# relay.net
KiCad netlist of a schematic drawn in Altium Designer
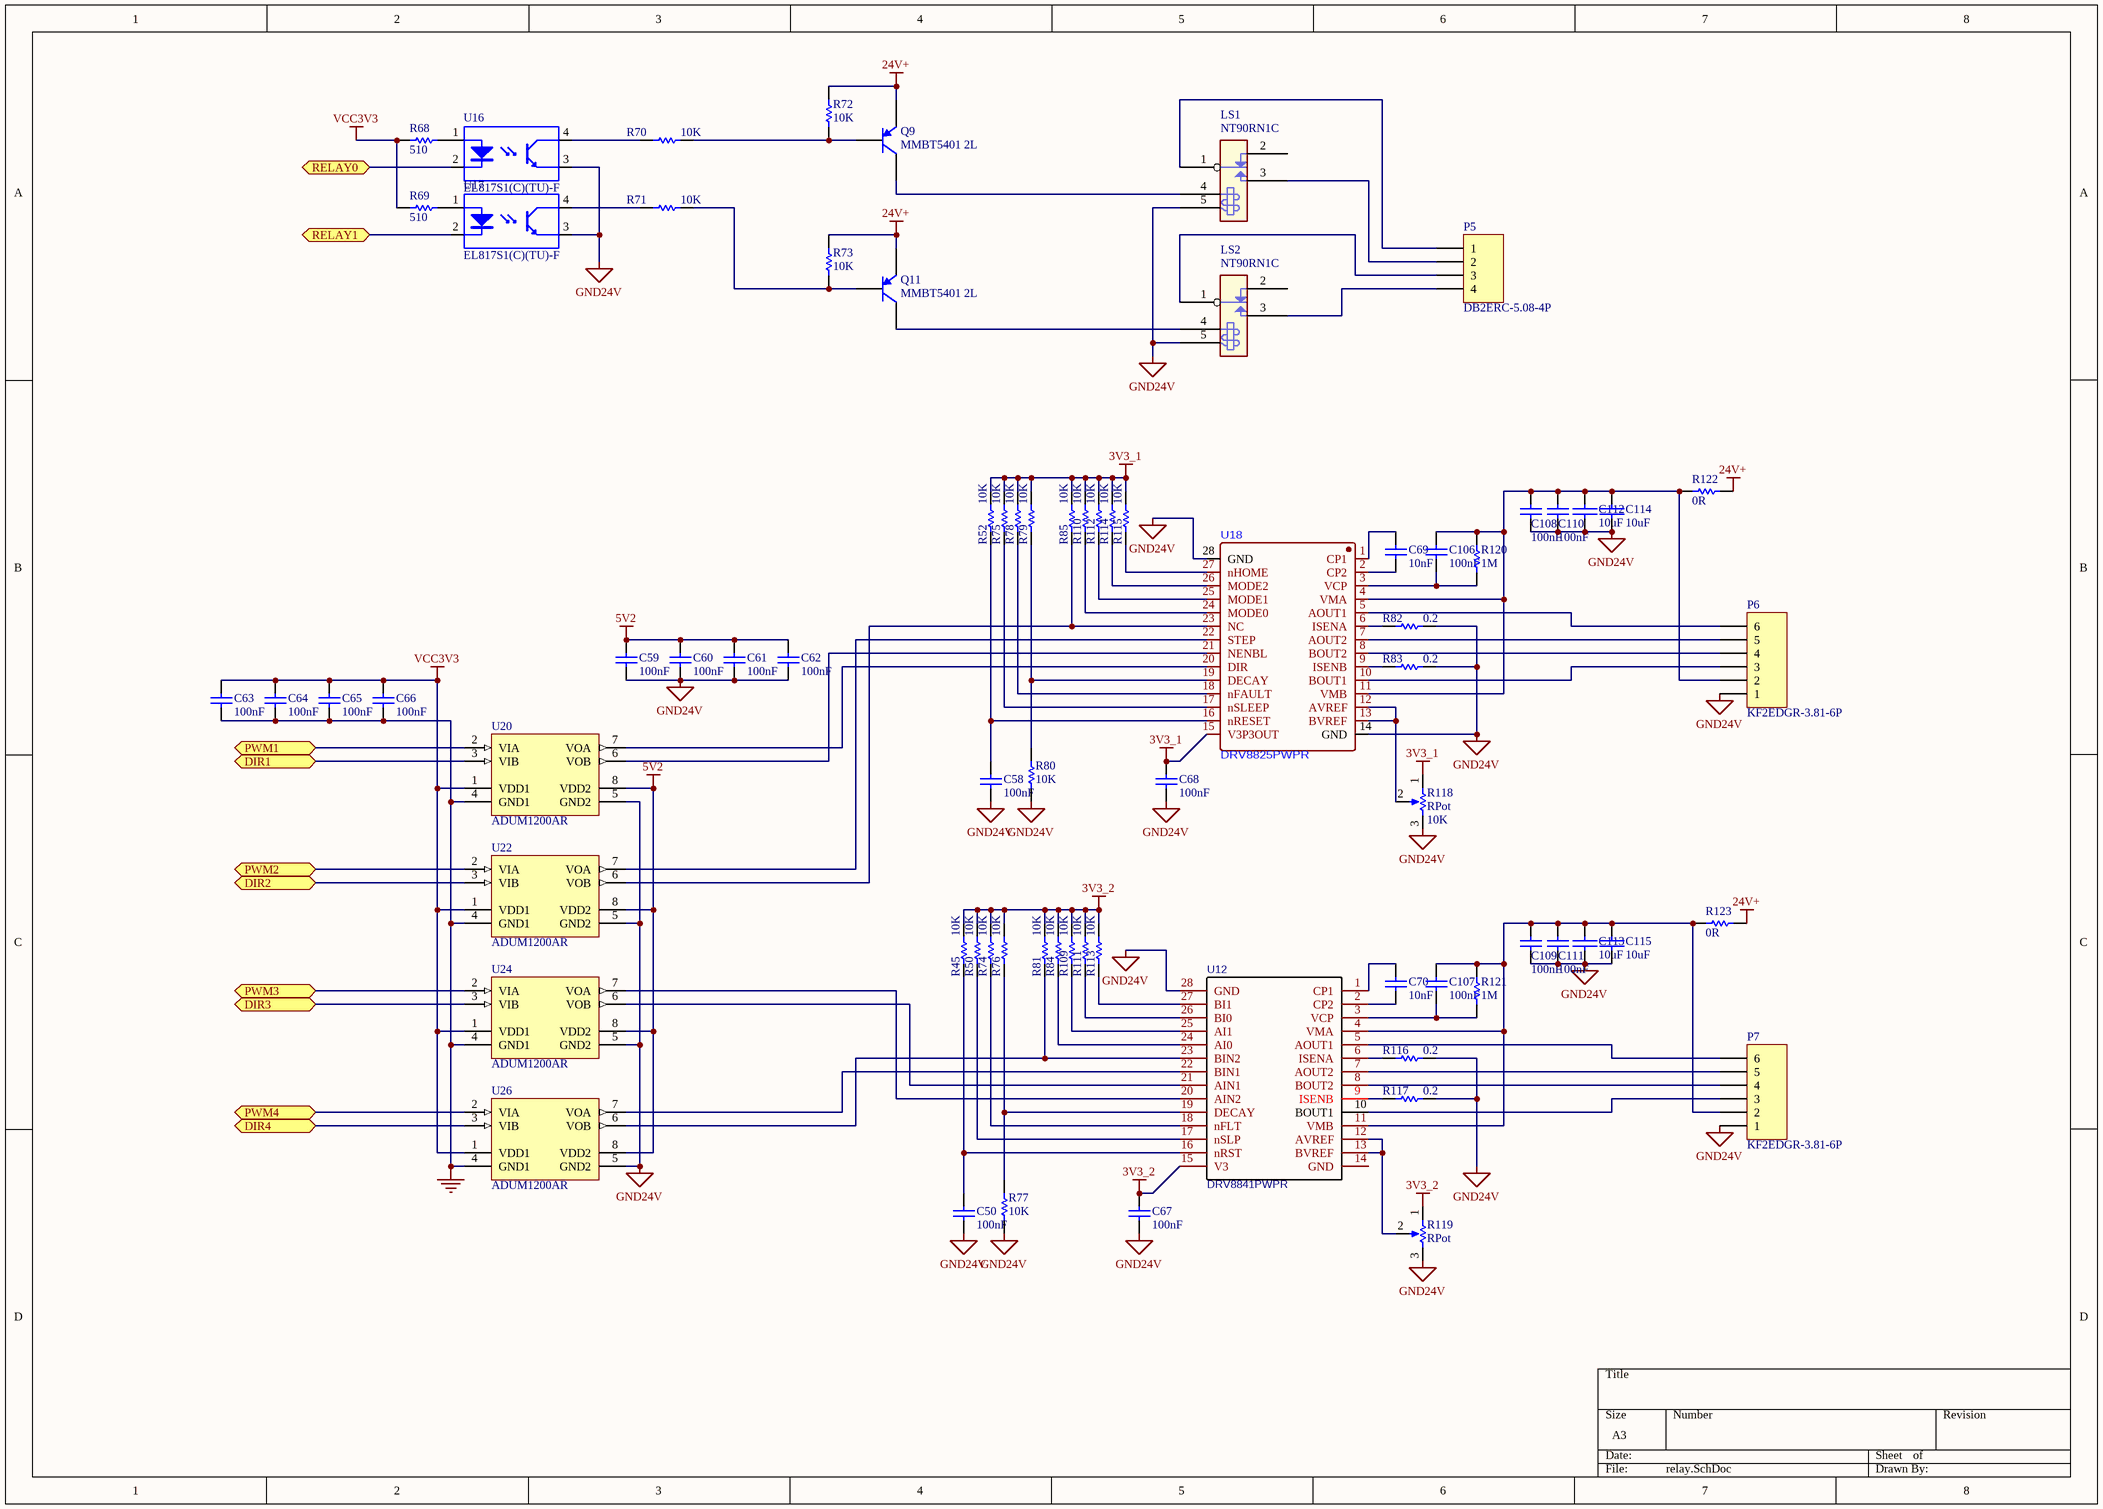
[diagram p0: relay.SchDoc]

(export (version "E")
  (design (tool "Eeschema 10.0.6"))
  (components
    (comp (ref "C50")
      (value "100nF")
      (footprint "0805_C")
      (description "贴片电容")
      (libsource (lib "Miscellaneous Devices LC") (part "0805 100nF(104) 10% 50V"))
    )
    (comp (ref "C58")
      (value "100nF")
      (footprint "0805_C")
      (description "贴片电容")
      (libsource (lib "Miscellaneous Devices LC") (part "0805 100nF(104) 10% 50V"))
    )
    (comp (ref "C59")
      (value "100nF")
      (footprint "0805_C")
      (description "贴片电容")
      (libsource (lib "Miscellaneous Devices LC") (part "0805 100nF(104) 10% 50V"))
    )
    (comp (ref "C60")
      (value "100nF")
      (footprint "0805_C")
      (description "贴片电容")
      (libsource (lib "Miscellaneous Devices LC") (part "0805 100nF(104) 10% 50V"))
    )
    (comp (ref "C61")
      (value "100nF")
      (footprint "0805_C")
      (description "贴片电容")
      (libsource (lib "Miscellaneous Devices LC") (part "0805 100nF(104) 10% 50V"))
    )
    (comp (ref "C62")
      (value "100nF")
      (footprint "0805_C")
      (description "贴片电容")
      (libsource (lib "Miscellaneous Devices LC") (part "0805 100nF(104) 10% 50V"))
    )
    (comp (ref "C63")
      (value "100nF")
      (footprint "0805_C")
      (description "贴片电容")
      (libsource (lib "Miscellaneous Devices LC") (part "0805 100nF(104) 10% 50V"))
    )
    (comp (ref "C64")
      (value "100nF")
      (footprint "0805_C")
      (description "贴片电容")
      (libsource (lib "Miscellaneous Devices LC") (part "0805 100nF(104) 10% 50V"))
    )
    (comp (ref "C65")
      (value "100nF")
      (footprint "0805_C")
      (description "贴片电容")
      (libsource (lib "Miscellaneous Devices LC") (part "0805 100nF(104) 10% 50V"))
    )
    (comp (ref "C66")
      (value "100nF")
      (footprint "0805_C")
      (description "贴片电容")
      (libsource (lib "Miscellaneous Devices LC") (part "0805 100nF(104) 10% 50V"))
    )
    (comp (ref "C67")
      (value "100nF")
      (footprint "0805_C")
      (description "贴片电容")
      (libsource (lib "Miscellaneous Devices LC") (part "0805 100nF(104) 10% 50V"))
    )
    (comp (ref "C68")
      (value "100nF")
      (footprint "0805_C")
      (description "贴片电容")
      (libsource (lib "Miscellaneous Devices LC") (part "0805 100nF(104) 10% 50V"))
    )
    (comp (ref "C69")
      (value "10nF")
      (footprint "0805_C")
      (description "贴片电容")
      (libsource (lib "Miscellaneous Devices LC") (part "0805 100nF(104) 10% 50V"))
    )
    (comp (ref "C70")
      (value "10nF")
      (footprint "0805_C")
      (description "贴片电容")
      (libsource (lib "Miscellaneous Devices LC") (part "0805 100nF(104) 10% 50V"))
    )
    (comp (ref "C106")
      (value "100nF")
      (footprint "0805_C")
      (description "贴片电容")
      (libsource (lib "Miscellaneous Devices LC") (part "0805 100nF(104) 10% 50V"))
    )
    (comp (ref "C107")
      (value "100nF")
      (footprint "0805_C")
      (description "贴片电容")
      (libsource (lib "Miscellaneous Devices LC") (part "0805 100nF(104) 10% 50V"))
    )
    (comp (ref "C108")
      (value "100nF")
      (footprint "0805_C")
      (description "贴片电容")
      (libsource (lib "Miscellaneous Devices LC") (part "0805 100nF(104) 10% 50V"))
    )
    (comp (ref "C109")
      (value "100nF")
      (footprint "0805_C")
      (description "贴片电容")
      (libsource (lib "Miscellaneous Devices LC") (part "0805 100nF(104) 10% 50V"))
    )
    (comp (ref "C110")
      (value "100nF")
      (footprint "0805_C")
      (description "贴片电容")
      (libsource (lib "Miscellaneous Devices LC") (part "0805 100nF(104) 10% 50V"))
    )
    (comp (ref "C111")
      (value "100nF")
      (footprint "0805_C")
      (description "贴片电容")
      (libsource (lib "Miscellaneous Devices LC") (part "0805 100nF(104) 10% 50V"))
    )
    (comp (ref "C112")
      (value "10uF")
      (footprint "0805_C")
      (description "Capacitor")
      (libsource (lib "*") (part "CC"))
    )
    (comp (ref "C113")
      (value "10uF")
      (footprint "0805_C")
      (description "Capacitor")
      (libsource (lib "*") (part "CC"))
    )
    (comp (ref "C114")
      (value "10uF")
      (footprint "0805_C")
      (description "Capacitor")
      (libsource (lib "*") (part "CC"))
    )
    (comp (ref "C115")
      (value "10uF")
      (footprint "0805_C")
      (description "Capacitor")
      (libsource (lib "*") (part "CC"))
    )
    (comp (ref "LS1") (value "NT90RN1C") (libsource (lib "Devices") (part "NT90RN1C")))
    (comp (ref "LS2") (value "NT90RN1C") (libsource (lib "Devices") (part "NT90RN1C")))
    (comp (ref "P5")
      (value "DB2ERC-5.08-4P")
      (footprint "MSTBV 2.5/4-G-5.08")
      (description "Header, 4-Pin, Right Angle")
      (fields (field (name "PUBLISHER") "Altium Limited"))
      (libsource (lib "Miscellaneous Connectors") (part "Header 4H"))
    )
    (comp (ref "P6")
      (value "KF2EDGR-3.81-6P")
      (footprint "MC1.5/6-ST-3.81")
      (description "Header, 6-Pin")
      (fields (field (name "PUBLISHER") "Altium Limited"))
      (libsource (lib "Miscellaneous Connectors") (part "Header 6"))
    )
    (comp (ref "P7")
      (value "KF2EDGR-3.81-6P")
      (footprint "MC1.5/6-ST-3.81")
      (description "Header, 6-Pin")
      (fields (field (name "PUBLISHER") "Altium Limited"))
      (libsource (lib "Miscellaneous Connectors") (part "Header 6"))
    )
    (comp (ref "Q9")
      (value "MMBT5401 2L")
      (footprint "SOT-23(SOT-23-3)")
      (description "三极管")
      (libsource (lib "Miscellaneous Devices LC") (part "SOT-23 MMBT5401 2L"))
    )
    (comp (ref "Q11")
      (value "MMBT5401 2L")
      (footprint "SOT-23(SOT-23-3)")
      (description "三极管")
      (libsource (lib "Miscellaneous Devices LC") (part "SOT-23 MMBT5401 2L"))
    )
    (comp (ref "R45")
      (value "10K")
      (footprint "0805_R")
      (description "Resistor")
      (fields (field (name "PUBLISHER") "Altium Limited"))
      (libsource (lib "Miscellaneous Devices") (part "Res1"))
    )
    (comp (ref "R50")
      (value "10K")
      (footprint "0805_R")
      (description "Resistor")
      (fields (field (name "PUBLISHER") "Altium Limited"))
      (libsource (lib "Miscellaneous Devices") (part "Res1"))
    )
    (comp (ref "R52")
      (value "10K")
      (footprint "0805_R")
      (description "Resistor")
      (fields (field (name "PUBLISHER") "Altium Limited"))
      (libsource (lib "Miscellaneous Devices") (part "Res1"))
    )
    (comp (ref "R68")
      (value "510")
      (footprint "0805_R")
      (description "Resistor")
      (fields (field (name "PUBLISHER") "Altium Limited"))
      (libsource (lib "Miscellaneous Devices") (part "Res1"))
    )
    (comp (ref "R69")
      (value "510")
      (footprint "0805_R")
      (description "Resistor")
      (fields (field (name "PUBLISHER") "Altium Limited"))
      (libsource (lib "Miscellaneous Devices") (part "Res1"))
    )
    (comp (ref "R70")
      (value "10K")
      (footprint "0805_R")
      (description "Resistor")
      (fields (field (name "PUBLISHER") "Altium Limited"))
      (libsource (lib "Miscellaneous Devices") (part "Res1"))
    )
    (comp (ref "R71")
      (value "10K")
      (footprint "0805_R")
      (description "Resistor")
      (fields (field (name "PUBLISHER") "Altium Limited"))
      (libsource (lib "Miscellaneous Devices") (part "Res1"))
    )
    (comp (ref "R72")
      (value "10K")
      (footprint "0805_R")
      (description "Resistor")
      (fields (field (name "PUBLISHER") "Altium Limited"))
      (libsource (lib "Miscellaneous Devices") (part "Res1"))
    )
    (comp (ref "R73")
      (value "10K")
      (footprint "0805_R")
      (description "Resistor")
      (fields (field (name "PUBLISHER") "Altium Limited"))
      (libsource (lib "Miscellaneous Devices") (part "Res1"))
    )
    (comp (ref "R74")
      (value "10K")
      (footprint "0805_R")
      (description "Resistor")
      (fields (field (name "PUBLISHER") "Altium Limited"))
      (libsource (lib "Miscellaneous Devices") (part "Res1"))
    )
    (comp (ref "R75")
      (value "10K")
      (footprint "0805_R")
      (description "Resistor")
      (fields (field (name "PUBLISHER") "Altium Limited"))
      (libsource (lib "Miscellaneous Devices") (part "Res1"))
    )
    (comp (ref "R76")
      (value "10K")
      (footprint "0805_R")
      (description "Resistor")
      (fields (field (name "PUBLISHER") "Altium Limited"))
      (libsource (lib "Miscellaneous Devices") (part "Res1"))
    )
    (comp (ref "R77")
      (value "10K")
      (footprint "0805_R")
      (description "Resistor")
      (fields (field (name "PUBLISHER") "Altium Limited"))
      (libsource (lib "Miscellaneous Devices") (part "Res1"))
    )
    (comp (ref "R78")
      (value "10K")
      (footprint "0805_R")
      (description "Resistor")
      (fields (field (name "PUBLISHER") "Altium Limited"))
      (libsource (lib "Miscellaneous Devices") (part "Res1"))
    )
    (comp (ref "R79")
      (value "10K")
      (footprint "0805_R")
      (description "Resistor")
      (fields (field (name "PUBLISHER") "Altium Limited"))
      (libsource (lib "Miscellaneous Devices") (part "Res1"))
    )
    (comp (ref "R80")
      (value "10K")
      (footprint "0805_R")
      (description "Resistor")
      (fields (field (name "PUBLISHER") "Altium Limited"))
      (libsource (lib "Miscellaneous Devices") (part "Res1"))
    )
    (comp (ref "R81")
      (value "10K")
      (footprint "0805_R")
      (description "Resistor")
      (fields (field (name "PUBLISHER") "Altium Limited"))
      (libsource (lib "Miscellaneous Devices") (part "Res1"))
    )
    (comp (ref "R82")
      (value "0.2")
      (footprint "R1210")
      (description "Resistor")
      (fields (field (name "PUBLISHER") "Altium Limited"))
      (libsource (lib "Miscellaneous Devices") (part "Res1"))
    )
    (comp (ref "R83")
      (value "0.2")
      (footprint "R1210")
      (description "Resistor")
      (fields (field (name "PUBLISHER") "Altium Limited"))
      (libsource (lib "Miscellaneous Devices") (part "Res1"))
    )
    (comp (ref "R84")
      (value "10K")
      (footprint "0805_R")
      (description "Resistor")
      (fields (field (name "PUBLISHER") "Altium Limited"))
      (libsource (lib "Miscellaneous Devices") (part "Res1"))
    )
    (comp (ref "R85")
      (value "10K")
      (footprint "0805_R")
      (description "Resistor")
      (fields (field (name "PUBLISHER") "Altium Limited"))
      (libsource (lib "Miscellaneous Devices") (part "Res1"))
    )
    (comp (ref "R109")
      (value "10K")
      (footprint "0805_R")
      (description "Resistor")
      (fields (field (name "PUBLISHER") "Altium Limited"))
      (libsource (lib "Miscellaneous Devices") (part "Res1"))
    )
    (comp (ref "R110")
      (value "10K")
      (footprint "0805_R")
      (description "Resistor")
      (fields (field (name "PUBLISHER") "Altium Limited"))
      (libsource (lib "Miscellaneous Devices") (part "Res1"))
    )
    (comp (ref "R111")
      (value "10K")
      (footprint "0805_R")
      (description "Resistor")
      (fields (field (name "PUBLISHER") "Altium Limited"))
      (libsource (lib "Miscellaneous Devices") (part "Res1"))
    )
    (comp (ref "R112")
      (value "10K")
      (footprint "0805_R")
      (description "Resistor")
      (fields (field (name "PUBLISHER") "Altium Limited"))
      (libsource (lib "Miscellaneous Devices") (part "Res1"))
    )
    (comp (ref "R113")
      (value "10K")
      (footprint "0805_R")
      (description "Resistor")
      (fields (field (name "PUBLISHER") "Altium Limited"))
      (libsource (lib "Miscellaneous Devices") (part "Res1"))
    )
    (comp (ref "R114")
      (value "10K")
      (footprint "0805_R")
      (description "Resistor")
      (fields (field (name "PUBLISHER") "Altium Limited"))
      (libsource (lib "Miscellaneous Devices") (part "Res1"))
    )
    (comp (ref "R115")
      (value "10K")
      (footprint "0805_R")
      (description "Resistor")
      (fields (field (name "PUBLISHER") "Altium Limited"))
      (libsource (lib "Miscellaneous Devices") (part "Res1"))
    )
    (comp (ref "R116")
      (value "0.2")
      (footprint "R1210")
      (description "Resistor")
      (fields (field (name "PUBLISHER") "Altium Limited"))
      (libsource (lib "Miscellaneous Devices") (part "Res1"))
    )
    (comp (ref "R117")
      (value "0.2")
      (footprint "R1210")
      (description "Resistor")
      (fields (field (name "PUBLISHER") "Altium Limited"))
      (libsource (lib "Miscellaneous Devices") (part "Res1"))
    )
    (comp (ref "R118")
      (value "RPot")
      (footprint "RES-ADJ-TH_3362P")
      (description "Potentiometer")
      (fields (field (name "ALTIUM_VALUE") "10K") (field (name "PUBLISHER") "Altium Limited"))
      (libsource (lib "Miscellaneous Devices") (part "RPot"))
    )
    (comp (ref "R119")
      (value "RPot")
      (footprint "RES-ADJ-TH_3362P")
      (description "Potentiometer")
      (fields (field (name "PUBLISHER") "Altium Limited"))
      (libsource (lib "Miscellaneous Devices") (part "RPot"))
    )
    (comp (ref "R120")
      (value "1M")
      (footprint "0805_R")
      (description "Resistor")
      (fields (field (name "PUBLISHER") "Altium Limited"))
      (libsource (lib "Miscellaneous Devices") (part "Res1"))
    )
    (comp (ref "R121")
      (value "1M")
      (footprint "0805_R")
      (description "Resistor")
      (fields (field (name "PUBLISHER") "Altium Limited"))
      (libsource (lib "Miscellaneous Devices") (part "Res1"))
    )
    (comp (ref "R122")
      (value "0R")
      (footprint "0805_R")
      (description "Resistor")
      (fields (field (name "PUBLISHER") "Altium Limited"))
      (libsource (lib "Miscellaneous Devices") (part "Res1"))
    )
    (comp (ref "R123")
      (value "0R")
      (footprint "0805_R")
      (description "Resistor")
      (fields (field (name "PUBLISHER") "Altium Limited"))
      (libsource (lib "Miscellaneous Devices") (part "Res1"))
    )
    (comp (ref "U12")
      (value "DRV8841PWPR")
      (footprint "HTSSOP-28_L9.8-W4.5-P0.65-LS6.6-BL-EP")
      (fields (field (name "BOM_SUPPLIER PART") "C36542"))
      (libsource (lib "IC") (part "DRV8841PWPR"))
    )
    (comp (ref "U16")
      (value "EL817S1(C)(TU)-F")
      (footprint "LC-SMD-4")
      (libsource (lib "IC") (part "TLP521"))
    )
    (comp (ref "U17")
      (value "EL817S1(C)(TU)-F")
      (footprint "LC-SMD-4")
      (libsource (lib "IC") (part "TLP521"))
    )
    (comp (ref "U18")
      (value "DRV8825PWPR")
      (footprint "HTSSOP_24P_L10.0-W4.4-P0.65-BL-EP")
      (libsource (lib "altium-import") (part "root_0_mirrored_DRV8825PWPR_"))
    )
    (comp (ref "U20")
      (value "ADUM1200AR")
      (footprint "ADI-R-8_N")
      (fields (field (name "MANUFACTURER") "Analog Devices"))
      (libsource (lib "Analog Devices Interface and Isolation Digital Isolators") (part "ADUM1200AR"))
    )
    (comp (ref "U22")
      (value "ADUM1200AR")
      (footprint "ADI-R-8_N")
      (fields (field (name "MANUFACTURER") "Analog Devices"))
      (libsource (lib "Analog Devices Interface and Isolation Digital Isolators") (part "ADUM1200AR"))
    )
    (comp (ref "U24")
      (value "ADUM1200AR")
      (footprint "ADI-R-8_N")
      (fields (field (name "MANUFACTURER") "Analog Devices"))
      (libsource (lib "Analog Devices Interface and Isolation Digital Isolators") (part "ADUM1200AR"))
    )
    (comp (ref "U26")
      (value "ADUM1200AR")
      (footprint "ADI-R-8_N")
      (fields (field (name "MANUFACTURER") "Analog Devices"))
      (libsource (lib "Analog Devices Interface and Isolation Digital Isolators") (part "ADUM1200AR"))
    )
  )
  (nets
    (net (code "1") (name "/DIR1") (class "Default")
      (node (ref "U20") (pin "3") (pinfunction "VIB_3") (pintype "input"))
    )
    (net (code "2") (name "/DIR2") (class "Default")
      (node (ref "U22") (pin "3") (pinfunction "VIB_3") (pintype "input"))
    )
    (net (code "3") (name "/DIR3") (class "Default")
      (node (ref "U24") (pin "3") (pinfunction "VIB_3") (pintype "input"))
    )
    (net (code "4") (name "/DIR4") (class "Default")
      (node (ref "U26") (pin "3") (pinfunction "VIB_3") (pintype "input"))
    )
    (net (code "5") (name "/PWM1") (class "Default")
      (node (ref "U20") (pin "2") (pinfunction "VIA_2") (pintype "input"))
    )
    (net (code "6") (name "/PWM2") (class "Default")
      (node (ref "U22") (pin "2") (pinfunction "VIA_2") (pintype "input"))
    )
    (net (code "7") (name "/PWM3") (class "Default")
      (node (ref "U24") (pin "2") (pinfunction "VIA_2") (pintype "input"))
    )
    (net (code "8") (name "/PWM4") (class "Default")
      (node (ref "U26") (pin "2") (pinfunction "VIA_2") (pintype "input"))
    )
    (net (code "9") (name "/RELAY0") (class "Default")
      (node (ref "U16") (pin "2") (pinfunction "K_2") (pintype "passive"))
    )
    (net (code "10") (name "/RELAY1") (class "Default")
      (node (ref "U17") (pin "2") (pinfunction "K_2") (pintype "passive"))
    )
    (net (code "11") (name "3V3_1") (class "Default")
      (node (ref "C68") (pin "1") (pinfunction "1_1") (pintype "passive"))
      (node (ref "R110") (pin "1") (pinfunction "1_1") (pintype "passive"))
      (node (ref "R112") (pin "1") (pinfunction "1_1") (pintype "passive"))
      (node (ref "R114") (pin "1") (pinfunction "1_1") (pintype "passive"))
      (node (ref "R115") (pin "1") (pinfunction "1_1") (pintype "passive"))
      (node (ref "R118") (pin "1") (pinfunction "TOP_1") (pintype "passive"))
      (node (ref "R52") (pin "1") (pinfunction "1_1") (pintype "passive"))
      (node (ref "R75") (pin "1") (pinfunction "1_1") (pintype "passive"))
      (node (ref "R78") (pin "1") (pinfunction "1_1") (pintype "passive"))
      (node (ref "R79") (pin "1") (pinfunction "1_1") (pintype "passive"))
      (node (ref "R85") (pin "1") (pinfunction "1_1") (pintype "passive"))
      (node (ref "U18") (pin "15") (pinfunction "V3P3OUT_15") (pintype "passive"))
    )
    (net (code "12") (name "3V3_2") (class "Default")
      (node (ref "C67") (pin "1") (pinfunction "1_1") (pintype "passive"))
      (node (ref "R109") (pin "1") (pinfunction "1_1") (pintype "passive"))
      (node (ref "R111") (pin "1") (pinfunction "1_1") (pintype "passive"))
      (node (ref "R113") (pin "1") (pinfunction "1_1") (pintype "passive"))
      (node (ref "R119") (pin "1") (pinfunction "TOP_1") (pintype "passive"))
      (node (ref "R45") (pin "1") (pinfunction "1_1") (pintype "passive"))
      (node (ref "R50") (pin "1") (pinfunction "1_1") (pintype "passive"))
      (node (ref "R74") (pin "1") (pinfunction "1_1") (pintype "passive"))
      (node (ref "R76") (pin "1") (pinfunction "1_1") (pintype "passive"))
      (node (ref "R81") (pin "1") (pinfunction "1_1") (pintype "passive"))
      (node (ref "R84") (pin "1") (pinfunction "1_1") (pintype "passive"))
      (node (ref "U12") (pin "15") (pinfunction "V3_15") (pintype "passive"))
    )
    (net (code "13") (name "5V2") (class "Default")
      (node (ref "C59") (pin "2") (pinfunction "2_2") (pintype "passive"))
      (node (ref "C60") (pin "2") (pinfunction "2_2") (pintype "passive"))
      (node (ref "C61") (pin "2") (pinfunction "2_2") (pintype "passive"))
      (node (ref "C62") (pin "2") (pinfunction "2_2") (pintype "passive"))
      (node (ref "U20") (pin "8") (pinfunction "VDD2_8") (pintype "power_in"))
      (node (ref "U22") (pin "8") (pinfunction "VDD2_8") (pintype "power_in"))
      (node (ref "U24") (pin "8") (pinfunction "VDD2_8") (pintype "power_in"))
      (node (ref "U26") (pin "8") (pinfunction "VDD2_8") (pintype "power_in"))
    )
    (net (code "14") (name "24V+") (class "Default")
      (node (ref "Q11") (pin "2") (pinfunction "E_2") (pintype "passive"))
      (node (ref "Q9") (pin "2") (pinfunction "E_2") (pintype "passive"))
      (node (ref "R122") (pin "2") (pinfunction "2_2") (pintype "passive"))
      (node (ref "R123") (pin "2") (pinfunction "2_2") (pintype "passive"))
      (node (ref "R72") (pin "2") (pinfunction "2_2") (pintype "passive"))
      (node (ref "R73") (pin "2") (pinfunction "2_2") (pintype "passive"))
    )
    (net (code "15") (name "GND") (class "Default")
      (node (ref "C63") (pin "1") (pinfunction "1_1") (pintype "passive"))
      (node (ref "C64") (pin "1") (pinfunction "1_1") (pintype "passive"))
      (node (ref "C65") (pin "1") (pinfunction "1_1") (pintype "passive"))
      (node (ref "C66") (pin "1") (pinfunction "1_1") (pintype "passive"))
      (node (ref "U20") (pin "4") (pinfunction "GND1_4") (pintype "power_in"))
      (node (ref "U22") (pin "4") (pinfunction "GND1_4") (pintype "power_in"))
      (node (ref "U24") (pin "4") (pinfunction "GND1_4") (pintype "power_in"))
      (node (ref "U26") (pin "4") (pinfunction "GND1_4") (pintype "power_in"))
    )
    (net (code "16") (name "GND24V") (class "Default")
      (node (ref "C108") (pin "1") (pinfunction "1_1") (pintype "passive"))
      (node (ref "C109") (pin "1") (pinfunction "1_1") (pintype "passive"))
      (node (ref "C110") (pin "1") (pinfunction "1_1") (pintype "passive"))
      (node (ref "C111") (pin "1") (pinfunction "1_1") (pintype "passive"))
      (node (ref "C112") (pin "1") (pinfunction "1_1") (pintype "passive"))
      (node (ref "C113") (pin "1") (pinfunction "1_1") (pintype "passive"))
      (node (ref "C114") (pin "1") (pinfunction "1_1") (pintype "passive"))
      (node (ref "C115") (pin "1") (pinfunction "1_1") (pintype "passive"))
      (node (ref "C50") (pin "2") (pinfunction "2_2") (pintype "passive"))
      (node (ref "C58") (pin "2") (pinfunction "2_2") (pintype "passive"))
      (node (ref "C59") (pin "1") (pinfunction "1_1") (pintype "passive"))
      (node (ref "C60") (pin "1") (pinfunction "1_1") (pintype "passive"))
      (node (ref "C61") (pin "1") (pinfunction "1_1") (pintype "passive"))
      (node (ref "C62") (pin "1") (pinfunction "1_1") (pintype "passive"))
      (node (ref "C67") (pin "2") (pinfunction "2_2") (pintype "passive"))
      (node (ref "C68") (pin "2") (pinfunction "2_2") (pintype "passive"))
      (node (ref "LS1") (pin "5") (pinfunction "COIL2_5") (pintype "passive"))
      (node (ref "LS2") (pin "5") (pinfunction "COIL2_5") (pintype "passive"))
      (node (ref "P6") (pin "1") (pinfunction "1_1") (pintype "passive"))
      (node (ref "P7") (pin "1") (pinfunction "1_1") (pintype "passive"))
      (node (ref "R116") (pin "1") (pinfunction "1_1") (pintype "passive"))
      (node (ref "R117") (pin "1") (pinfunction "1_1") (pintype "passive"))
      (node (ref "R118") (pin "3") (pinfunction "BOT_3") (pintype "passive"))
      (node (ref "R119") (pin "3") (pinfunction "BOT_3") (pintype "passive"))
      (node (ref "R77") (pin "2") (pinfunction "2_2") (pintype "passive"))
      (node (ref "R80") (pin "2") (pinfunction "2_2") (pintype "passive"))
      (node (ref "R82") (pin "1") (pinfunction "1_1") (pintype "passive"))
      (node (ref "R83") (pin "1") (pinfunction "1_1") (pintype "passive"))
      (node (ref "U12") (pin "28") (pinfunction "GND_28") (pintype "passive"))
      (node (ref "U16") (pin "3") (pinfunction "E_3") (pintype "passive"))
      (node (ref "U17") (pin "3") (pinfunction "E_3") (pintype "passive"))
      (node (ref "U18") (pin "14") (pinfunction "GND_14") (pintype "passive"))
      (node (ref "U18") (pin "28") (pinfunction "GND_28") (pintype "passive"))
      (node (ref "U20") (pin "5") (pinfunction "GND2_5") (pintype "power_in"))
      (node (ref "U22") (pin "5") (pinfunction "GND2_5") (pintype "power_in"))
      (node (ref "U24") (pin "5") (pinfunction "GND2_5") (pintype "power_in"))
      (node (ref "U26") (pin "5") (pinfunction "GND2_5") (pintype "power_in"))
    )
    (net (code "17") (name "Net-(LS1-COIL1)") (class "Default")
      (node (ref "LS1") (pin "4") (pinfunction "COIL1_4") (pintype "passive"))
      (node (ref "Q9") (pin "3") (pinfunction "C_3") (pintype "passive"))
    )
    (net (code "18") (name "Net-(LS1-COMMON)") (class "Default")
      (node (ref "LS1") (pin "1") (pinfunction "COMMON_1") (pintype "passive"))
      (node (ref "P5") (pin "1") (pinfunction "1_1") (pintype "passive"))
    )
    (net (code "19") (name "Net-(LS1-NO)") (class "Default")
      (node (ref "LS1") (pin "3") (pinfunction "NO_3") (pintype "passive"))
      (node (ref "P5") (pin "2") (pinfunction "2_2") (pintype "passive"))
    )
    (net (code "20") (name "Net-(LS2-COIL1)") (class "Default")
      (node (ref "LS2") (pin "4") (pinfunction "COIL1_4") (pintype "passive"))
      (node (ref "Q11") (pin "3") (pinfunction "C_3") (pintype "passive"))
    )
    (net (code "21") (name "Net-(LS2-COMMON)") (class "Default")
      (node (ref "LS2") (pin "1") (pinfunction "COMMON_1") (pintype "passive"))
      (node (ref "P5") (pin "3") (pinfunction "3_3") (pintype "passive"))
    )
    (net (code "22") (name "Net-(LS2-NO)") (class "Default")
      (node (ref "LS2") (pin "3") (pinfunction "NO_3") (pintype "passive"))
      (node (ref "P5") (pin "4") (pinfunction "4_4") (pintype "passive"))
    )
    (net (code "23") (name "Net-(Q9-B)") (class "Default")
      (node (ref "Q9") (pin "1") (pinfunction "B_1") (pintype "passive"))
      (node (ref "R70") (pin "2") (pinfunction "2_2") (pintype "passive"))
      (node (ref "R72") (pin "1") (pinfunction "1_1") (pintype "passive"))
    )
    (net (code "24") (name "Net-(Q11-B)") (class "Default")
      (node (ref "Q11") (pin "1") (pinfunction "B_1") (pintype "passive"))
      (node (ref "R71") (pin "2") (pinfunction "2_2") (pintype "passive"))
      (node (ref "R73") (pin "1") (pinfunction "1_1") (pintype "passive"))
    )
    (net (code "25") (name "Net-(R118-TAP)") (class "Default")
      (node (ref "R118") (pin "2") (pinfunction "TAP_2") (pintype "passive"))
      (node (ref "U18") (pin "12") (pinfunction "AVREF_12") (pintype "passive"))
      (node (ref "U18") (pin "13") (pinfunction "BVREF_13") (pintype "passive"))
    )
    (net (code "26") (name "Net-(R119-TAP)") (class "Default")
      (node (ref "R119") (pin "2") (pinfunction "TAP_2") (pintype "passive"))
      (node (ref "U12") (pin "12") (pinfunction "AVREF_12") (pintype "passive"))
      (node (ref "U12") (pin "13") (pinfunction "BVREF_13") (pintype "passive"))
    )
    (net (code "27") (name "Net-(U12-AI0)") (class "Default")
      (node (ref "R84") (pin "2") (pinfunction "2_2") (pintype "passive"))
      (node (ref "U12") (pin "24") (pinfunction "AI0_24") (pintype "passive"))
    )
    (net (code "28") (name "Net-(U12-AI1)") (class "Default")
      (node (ref "R109") (pin "2") (pinfunction "2_2") (pintype "passive"))
      (node (ref "U12") (pin "25") (pinfunction "AI1_25") (pintype "passive"))
    )
    (net (code "29") (name "Net-(U12-AIN1)") (class "Default")
      (node (ref "U12") (pin "21") (pinfunction "AIN1_21") (pintype "passive"))
      (node (ref "U24") (pin "6") (pinfunction "VOB_6") (pintype "output"))
    )
    (net (code "30") (name "Net-(U12-AIN2)") (class "Default")
      (node (ref "U12") (pin "20") (pinfunction "AIN2_20") (pintype "passive"))
      (node (ref "U24") (pin "7") (pinfunction "VOA_7") (pintype "output"))
    )
    (net (code "31") (name "Net-(U12-AOUT1)") (class "Default")
      (node (ref "P7") (pin "6") (pinfunction "6_6") (pintype "passive"))
      (node (ref "U12") (pin "5") (pinfunction "AOUT1_5") (pintype "passive"))
    )
    (net (code "32") (name "Net-(U12-AOUT2)") (class "Default")
      (node (ref "P7") (pin "5") (pinfunction "5_5") (pintype "passive"))
      (node (ref "U12") (pin "7") (pinfunction "AOUT2_7") (pintype "passive"))
    )
    (net (code "33") (name "Net-(U12-BI0)") (class "Default")
      (node (ref "R111") (pin "2") (pinfunction "2_2") (pintype "passive"))
      (node (ref "U12") (pin "26") (pinfunction "BI0_26") (pintype "passive"))
    )
    (net (code "34") (name "Net-(U12-BI1)") (class "Default")
      (node (ref "R113") (pin "2") (pinfunction "2_2") (pintype "passive"))
      (node (ref "U12") (pin "27") (pinfunction "BI1_27") (pintype "passive"))
    )
    (net (code "35") (name "Net-(U12-BIN1)") (class "Default")
      (node (ref "U12") (pin "22") (pinfunction "BIN1_22") (pintype "passive"))
      (node (ref "U26") (pin "7") (pinfunction "VOA_7") (pintype "output"))
    )
    (net (code "36") (name "Net-(U12-BIN2)") (class "Default")
      (node (ref "R81") (pin "2") (pinfunction "2_2") (pintype "passive"))
      (node (ref "U12") (pin "23") (pinfunction "BIN2_23") (pintype "passive"))
      (node (ref "U26") (pin "6") (pinfunction "VOB_6") (pintype "output"))
    )
    (net (code "37") (name "Net-(U12-BOUT1)") (class "Default")
      (node (ref "P7") (pin "3") (pinfunction "3_3") (pintype "passive"))
      (node (ref "U12") (pin "10") (pinfunction "BOUT1_10") (pintype "passive"))
    )
    (net (code "38") (name "Net-(U12-BOUT2)") (class "Default")
      (node (ref "P7") (pin "4") (pinfunction "4_4") (pintype "passive"))
      (node (ref "U12") (pin "8") (pinfunction "BOUT2_8") (pintype "passive"))
    )
    (net (code "39") (name "Net-(U12-CP1)") (class "Default")
      (node (ref "C70") (pin "1") (pinfunction "1_1") (pintype "passive"))
      (node (ref "U12") (pin "1") (pinfunction "CP1_1") (pintype "passive"))
    )
    (net (code "40") (name "Net-(U12-CP2)") (class "Default")
      (node (ref "C70") (pin "2") (pinfunction "2_2") (pintype "passive"))
      (node (ref "U12") (pin "2") (pinfunction "CP2_2") (pintype "passive"))
    )
    (net (code "41") (name "Net-(U12-DECAY)") (class "Default")
      (node (ref "R76") (pin "2") (pinfunction "2_2") (pintype "passive"))
      (node (ref "R77") (pin "1") (pinfunction "1_1") (pintype "passive"))
      (node (ref "U12") (pin "19") (pinfunction "DECAY_19") (pintype "passive"))
    )
    (net (code "42") (name "Net-(U12-ISENA)") (class "Default")
      (node (ref "R116") (pin "2") (pinfunction "2_2") (pintype "passive"))
      (node (ref "U12") (pin "6") (pinfunction "ISENA_6") (pintype "passive"))
    )
    (net (code "43") (name "Net-(U12-ISENB)") (class "Default")
      (node (ref "R117") (pin "2") (pinfunction "2_2") (pintype "passive"))
      (node (ref "U12") (pin "9") (pinfunction "ISENB_9") (pintype "passive"))
    )
    (net (code "44") (name "Net-(U12-VCP)") (class "Default")
      (node (ref "C107") (pin "1") (pinfunction "1_1") (pintype "passive"))
      (node (ref "R121") (pin "2") (pinfunction "2_2") (pintype "passive"))
      (node (ref "U12") (pin "3") (pinfunction "VCP_3") (pintype "passive"))
    )
    (net (code "45") (name "Net-(U12-VMA)") (class "Default")
      (node (ref "C107") (pin "2") (pinfunction "2_2") (pintype "passive"))
      (node (ref "C109") (pin "2") (pinfunction "2_2") (pintype "passive"))
      (node (ref "C111") (pin "2") (pinfunction "2_2") (pintype "passive"))
      (node (ref "C113") (pin "2") (pinfunction "2_2") (pintype "passive"))
      (node (ref "C115") (pin "2") (pinfunction "2_2") (pintype "passive"))
      (node (ref "P7") (pin "2") (pinfunction "2_2") (pintype "passive"))
      (node (ref "R121") (pin "1") (pinfunction "1_1") (pintype "passive"))
      (node (ref "R123") (pin "1") (pinfunction "1_1") (pintype "passive"))
      (node (ref "U12") (pin "11") (pinfunction "VMB_11") (pintype "passive"))
      (node (ref "U12") (pin "4") (pinfunction "VMA_4") (pintype "passive"))
    )
    (net (code "46") (name "Net-(U12-nFLT)") (class "Default")
      (node (ref "R74") (pin "2") (pinfunction "2_2") (pintype "passive"))
      (node (ref "U12") (pin "18") (pinfunction "nFLT_18") (pintype "passive"))
    )
    (net (code "47") (name "Net-(U12-nRST)") (class "Default")
      (node (ref "C50") (pin "1") (pinfunction "1_1") (pintype "passive"))
      (node (ref "R45") (pin "2") (pinfunction "2_2") (pintype "passive"))
      (node (ref "U12") (pin "16") (pinfunction "nRST_16") (pintype "passive"))
    )
    (net (code "48") (name "Net-(U12-nSLP)") (class "Default")
      (node (ref "R50") (pin "2") (pinfunction "2_2") (pintype "passive"))
      (node (ref "U12") (pin "17") (pinfunction "nSLP_17") (pintype "passive"))
    )
    (net (code "49") (name "Net-(U16-A)") (class "Default")
      (node (ref "R68") (pin "1") (pinfunction "1_1") (pintype "passive"))
      (node (ref "U16") (pin "1") (pinfunction "A_1") (pintype "passive"))
    )
    (net (code "50") (name "Net-(U16-C)") (class "Default")
      (node (ref "R70") (pin "1") (pinfunction "1_1") (pintype "passive"))
      (node (ref "U16") (pin "4") (pinfunction "C_4") (pintype "passive"))
    )
    (net (code "51") (name "Net-(U17-A)") (class "Default")
      (node (ref "R69") (pin "1") (pinfunction "1_1") (pintype "passive"))
      (node (ref "U17") (pin "1") (pinfunction "A_1") (pintype "passive"))
    )
    (net (code "52") (name "Net-(U17-C)") (class "Default")
      (node (ref "R71") (pin "1") (pinfunction "1_1") (pintype "passive"))
      (node (ref "U17") (pin "4") (pinfunction "C_4") (pintype "passive"))
    )
    (net (code "53") (name "Net-(U18-AOUT1)") (class "Default")
      (node (ref "P6") (pin "6") (pinfunction "6_6") (pintype "passive"))
      (node (ref "U18") (pin "5") (pinfunction "AOUT1_5") (pintype "passive"))
    )
    (net (code "54") (name "Net-(U18-AOUT2)") (class "Default")
      (node (ref "P6") (pin "5") (pinfunction "5_5") (pintype "passive"))
      (node (ref "U18") (pin "7") (pinfunction "AOUT2_7") (pintype "passive"))
    )
    (net (code "55") (name "Net-(U18-BOUT1)") (class "Default")
      (node (ref "P6") (pin "3") (pinfunction "3_3") (pintype "passive"))
      (node (ref "U18") (pin "10") (pinfunction "BOUT1_10") (pintype "passive"))
    )
    (net (code "56") (name "Net-(U18-BOUT2)") (class "Default")
      (node (ref "P6") (pin "4") (pinfunction "4_4") (pintype "passive"))
      (node (ref "U18") (pin "8") (pinfunction "BOUT2_8") (pintype "passive"))
    )
    (net (code "57") (name "Net-(U18-CP1)") (class "Default")
      (node (ref "C69") (pin "1") (pinfunction "1_1") (pintype "passive"))
      (node (ref "U18") (pin "1") (pinfunction "CP1_1") (pintype "passive"))
    )
    (net (code "58") (name "Net-(U18-CP2)") (class "Default")
      (node (ref "C69") (pin "2") (pinfunction "2_2") (pintype "passive"))
      (node (ref "U18") (pin "2") (pinfunction "CP2_2") (pintype "passive"))
    )
    (net (code "59") (name "Net-(U18-DECAY)") (class "Default")
      (node (ref "R79") (pin "2") (pinfunction "2_2") (pintype "passive"))
      (node (ref "R80") (pin "1") (pinfunction "1_1") (pintype "passive"))
      (node (ref "U18") (pin "19") (pinfunction "DECAY_19") (pintype "passive"))
    )
    (net (code "60") (name "Net-(U18-DIR)") (class "Default")
      (node (ref "U18") (pin "20") (pinfunction "DIR_20") (pintype "passive"))
      (node (ref "U20") (pin "7") (pinfunction "VOA_7") (pintype "output"))
    )
    (net (code "61") (name "Net-(U18-ISENA)") (class "Default")
      (node (ref "R82") (pin "2") (pinfunction "2_2") (pintype "passive"))
      (node (ref "U18") (pin "6") (pinfunction "ISENA_6") (pintype "passive"))
    )
    (net (code "62") (name "Net-(U18-ISENB)") (class "Default")
      (node (ref "R83") (pin "2") (pinfunction "2_2") (pintype "passive"))
      (node (ref "U18") (pin "9") (pinfunction "ISENB_9") (pintype "passive"))
    )
    (net (code "63") (name "Net-(U18-MODE0)") (class "Default")
      (node (ref "R110") (pin "2") (pinfunction "2_2") (pintype "passive"))
      (node (ref "U18") (pin "24") (pinfunction "MODE0_24") (pintype "passive"))
    )
    (net (code "64") (name "Net-(U18-MODE1)") (class "Default")
      (node (ref "R112") (pin "2") (pinfunction "2_2") (pintype "passive"))
      (node (ref "U18") (pin "25") (pinfunction "MODE1_25") (pintype "passive"))
    )
    (net (code "65") (name "Net-(U18-MODE2)") (class "Default")
      (node (ref "R114") (pin "2") (pinfunction "2_2") (pintype "passive"))
      (node (ref "U18") (pin "26") (pinfunction "MODE2_26") (pintype "passive"))
    )
    (net (code "66") (name "Net-(U18-NC)") (class "Default")
      (node (ref "R85") (pin "2") (pinfunction "2_2") (pintype "passive"))
      (node (ref "U18") (pin "23") (pinfunction "NC_23") (pintype "passive"))
      (node (ref "U22") (pin "6") (pinfunction "VOB_6") (pintype "output"))
    )
    (net (code "67") (name "Net-(U18-NENBL)") (class "Default")
      (node (ref "U18") (pin "21") (pinfunction "NENBL_21") (pintype "passive"))
      (node (ref "U20") (pin "6") (pinfunction "VOB_6") (pintype "output"))
    )
    (net (code "68") (name "Net-(U18-STEP)") (class "Default")
      (node (ref "U18") (pin "22") (pinfunction "STEP_22") (pintype "passive"))
      (node (ref "U22") (pin "7") (pinfunction "VOA_7") (pintype "output"))
    )
    (net (code "69") (name "Net-(U18-VCP)") (class "Default")
      (node (ref "C106") (pin "1") (pinfunction "1_1") (pintype "passive"))
      (node (ref "R120") (pin "2") (pinfunction "2_2") (pintype "passive"))
      (node (ref "U18") (pin "3") (pinfunction "VCP_3") (pintype "passive"))
    )
    (net (code "70") (name "Net-(U18-VMA)") (class "Default")
      (node (ref "C106") (pin "2") (pinfunction "2_2") (pintype "passive"))
      (node (ref "C108") (pin "2") (pinfunction "2_2") (pintype "passive"))
      (node (ref "C110") (pin "2") (pinfunction "2_2") (pintype "passive"))
      (node (ref "C112") (pin "2") (pinfunction "2_2") (pintype "passive"))
      (node (ref "C114") (pin "2") (pinfunction "2_2") (pintype "passive"))
      (node (ref "P6") (pin "2") (pinfunction "2_2") (pintype "passive"))
      (node (ref "R120") (pin "1") (pinfunction "1_1") (pintype "passive"))
      (node (ref "R122") (pin "1") (pinfunction "1_1") (pintype "passive"))
      (node (ref "U18") (pin "11") (pinfunction "VMB_11") (pintype "passive"))
      (node (ref "U18") (pin "4") (pinfunction "VMA_4") (pintype "passive"))
    )
    (net (code "71") (name "Net-(U18-nFAULT)") (class "Default")
      (node (ref "R78") (pin "2") (pinfunction "2_2") (pintype "passive"))
      (node (ref "U18") (pin "18") (pinfunction "nFAULT_18") (pintype "passive"))
    )
    (net (code "72") (name "Net-(U18-nHOME)") (class "Default")
      (node (ref "R115") (pin "2") (pinfunction "2_2") (pintype "passive"))
      (node (ref "U18") (pin "27") (pinfunction "nHOME_27") (pintype "passive"))
    )
    (net (code "73") (name "Net-(U18-nRESET)") (class "Default")
      (node (ref "C58") (pin "1") (pinfunction "1_1") (pintype "passive"))
      (node (ref "R52") (pin "2") (pinfunction "2_2") (pintype "passive"))
      (node (ref "U18") (pin "16") (pinfunction "nRESET_16") (pintype "passive"))
    )
    (net (code "74") (name "Net-(U18-nSLEEP)") (class "Default")
      (node (ref "R75") (pin "2") (pinfunction "2_2") (pintype "passive"))
      (node (ref "U18") (pin "17") (pinfunction "nSLEEP_17") (pintype "passive"))
    )
    (net (code "75") (name "VCC3V3") (class "Default")
      (node (ref "C63") (pin "2") (pinfunction "2_2") (pintype "passive"))
      (node (ref "C64") (pin "2") (pinfunction "2_2") (pintype "passive"))
      (node (ref "C65") (pin "2") (pinfunction "2_2") (pintype "passive"))
      (node (ref "C66") (pin "2") (pinfunction "2_2") (pintype "passive"))
      (node (ref "R68") (pin "2") (pinfunction "2_2") (pintype "passive"))
      (node (ref "R69") (pin "2") (pinfunction "2_2") (pintype "passive"))
      (node (ref "U20") (pin "1") (pinfunction "VDD1_1") (pintype "power_in"))
      (node (ref "U22") (pin "1") (pinfunction "VDD1_1") (pintype "power_in"))
      (node (ref "U24") (pin "1") (pinfunction "VDD1_1") (pintype "power_in"))
      (node (ref "U26") (pin "1") (pinfunction "VDD1_1") (pintype "power_in"))
    )
    (net (code "76") (name "unconnected-(LS1-NC-Pad2)") (class "Default")
      (node (ref "LS1") (pin "2") (pinfunction "NC_2") (pintype "passive"))
    )
    (net (code "77") (name "unconnected-(LS2-NC-Pad2)") (class "Default")
      (node (ref "LS2") (pin "2") (pinfunction "NC_2") (pintype "passive"))
    )
    (net (code "78") (name "unconnected-(U12-GND-Pad14)") (class "Default")
      (node (ref "U12") (pin "14") (pinfunction "GND_14") (pintype "passive"))
    )
  )
)
